# BMS12v3.net
KiCad netlist of a schematic drawn in EAGLE
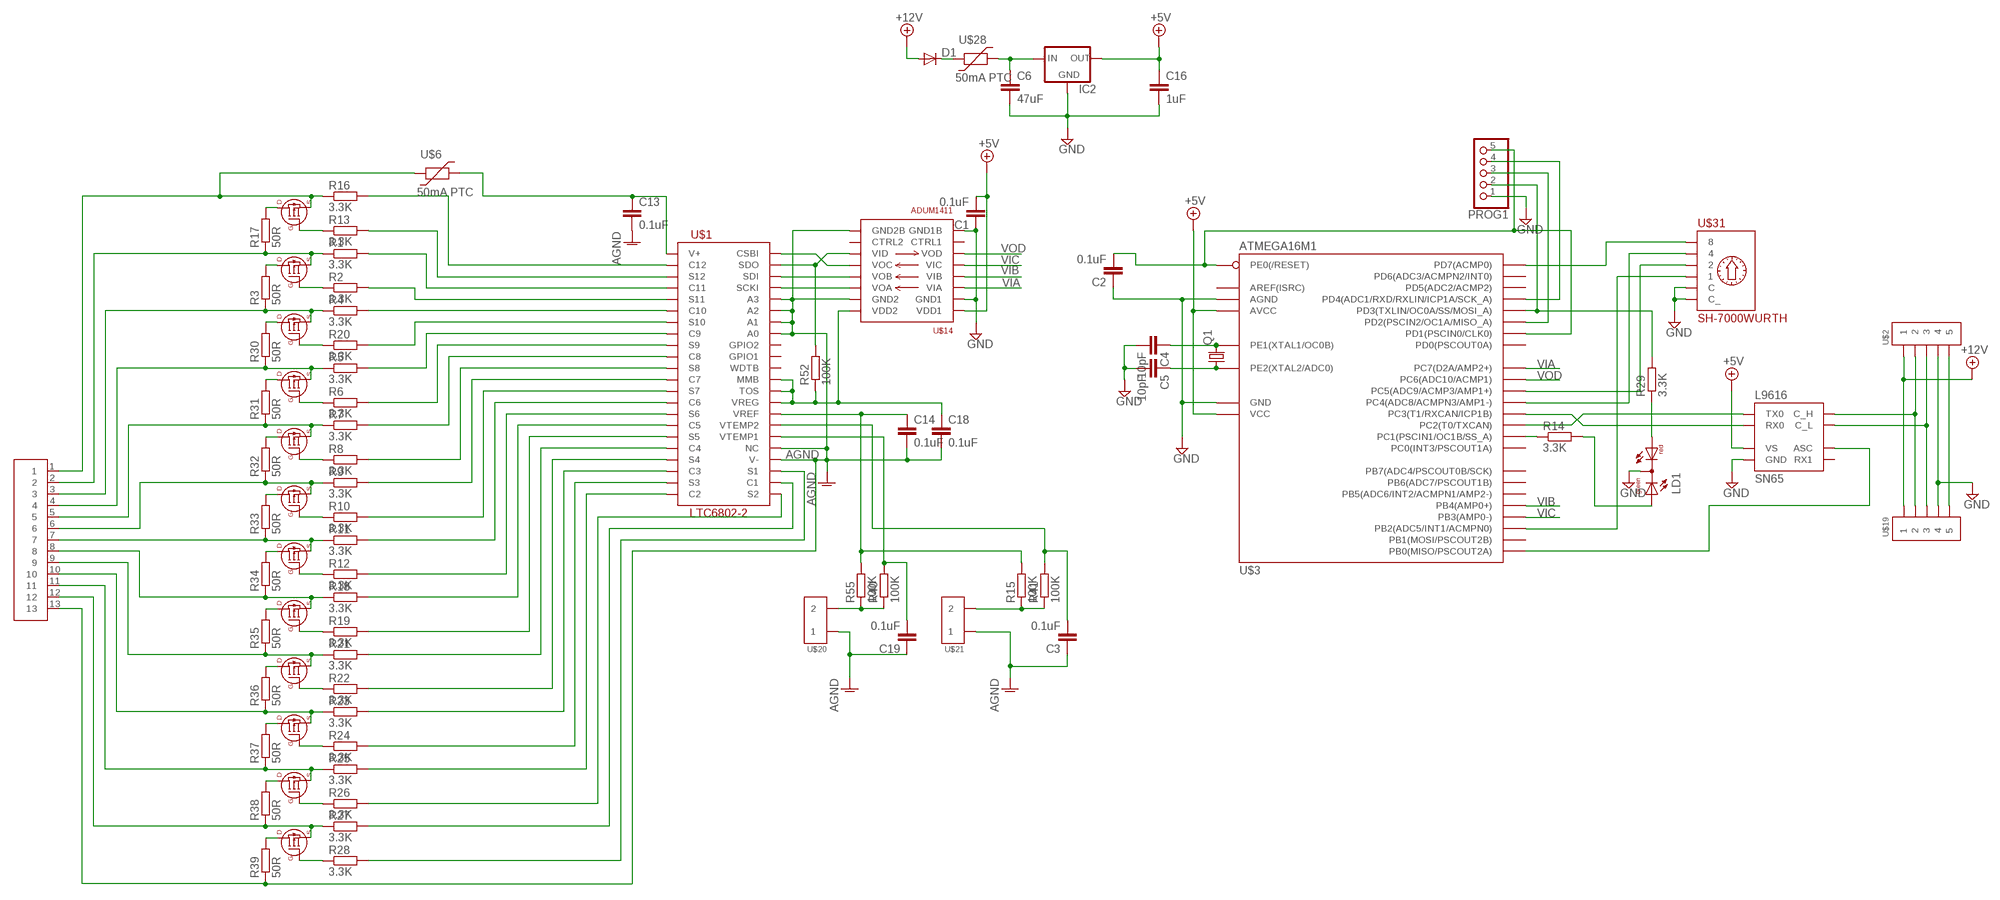
[diagram p0: schematic, sheet 1]

(export (version "E")
  (design (tool "Eeschema 10.0.6"))
  (components
    (comp (ref "C1")
      (value "0.1uF")
      (footprint "eagle-import:C0805")
      (libsource (lib "eagle-import") (part "C-EUC0805"))
    )
    (comp (ref "C2")
      (value "0.1uF")
      (footprint "eagle-import:C0805")
      (libsource (lib "eagle-import") (part "C-EUC0805"))
    )
    (comp (ref "C3")
      (value "0.1uF")
      (footprint "eagle-import:C0805")
      (libsource (lib "eagle-import") (part "C-EUC0805"))
    )
    (comp (ref "C4")
      (value "10pF")
      (footprint "eagle-import:C0805")
      (libsource (lib "eagle-import") (part "C-EUC0805"))
    )
    (comp (ref "C5")
      (value "10pF")
      (footprint "eagle-import:C0805")
      (libsource (lib "eagle-import") (part "C-EUC0805"))
    )
    (comp (ref "C6")
      (value "47uF")
      (footprint "eagle-import:C1206")
      (libsource (lib "eagle-import") (part "C-EUC1206"))
    )
    (comp (ref "C13")
      (value "0.1uF")
      (footprint "eagle-import:C0805")
      (libsource (lib "eagle-import") (part "C-EUC0805"))
    )
    (comp (ref "C14")
      (value "0.1uF")
      (footprint "eagle-import:C0805")
      (libsource (lib "eagle-import") (part "C-EUC0805"))
    )
    (comp (ref "C16")
      (value "1uF")
      (footprint "eagle-import:C0805")
      (libsource (lib "eagle-import") (part "C-EUC0805"))
    )
    (comp (ref "C18")
      (value "0.1uF")
      (footprint "eagle-import:C0805")
      (libsource (lib "eagle-import") (part "C-EUC0805"))
    )
    (comp (ref "C19")
      (value "0.1uF")
      (footprint "eagle-import:C0805")
      (libsource (lib "eagle-import") (part "C-EUC0805"))
    )
    (comp (ref "D1")
      (value "DIODE-SOD123")
      (footprint "eagle-import:SOD123")
      (libsource (lib "eagle-import") (part "DIODE-SOD123"))
    )
    (comp (ref "IC2")
      (value "78LXXSOT89")
      (footprint "eagle-import:SOT89R")
      (libsource (lib "eagle-import") (part "78LXXSOT89"))
    )
    (comp (ref "LD1")
      (value "DUOLED-RG-C")
      (footprint "eagle-import:DUOLED-C-5MM")
      (libsource (lib "eagle-import") (part "DUOLED-RG-C"))
    )
    (comp (ref "PROG1")
      (value "PINHD-1X5")
      (footprint "eagle-import:1X05")
      (libsource (lib "eagle-import") (part "PINHD-1X5"))
    )
    (comp (ref "Q1")
      (value "CRYSTALCTS406")
      (footprint "eagle-import:CTS406")
      (libsource (lib "eagle-import") (part "CRYSTALCTS406"))
    )
    (comp (ref "R1")
      (value "3.3K")
      (footprint "eagle-import:R0805")
      (libsource (lib "eagle-import") (part "R-EU_R0805"))
    )
    (comp (ref "R2")
      (value "3.3K")
      (footprint "eagle-import:R0805")
      (libsource (lib "eagle-import") (part "R-EU_R0805"))
    )
    (comp (ref "R3")
      (value "50R")
      (footprint "eagle-import:R2512")
      (libsource (lib "eagle-import") (part "R-EU_R2512"))
    )
    (comp (ref "R4")
      (value "3.3K")
      (footprint "eagle-import:R0805")
      (libsource (lib "eagle-import") (part "R-EU_R0805"))
    )
    (comp (ref "R5")
      (value "3.3K")
      (footprint "eagle-import:R0805")
      (libsource (lib "eagle-import") (part "R-EU_R0805"))
    )
    (comp (ref "R6")
      (value "3.3K")
      (footprint "eagle-import:R0805")
      (libsource (lib "eagle-import") (part "R-EU_R0805"))
    )
    (comp (ref "R7")
      (value "3.3K")
      (footprint "eagle-import:R0805")
      (libsource (lib "eagle-import") (part "R-EU_R0805"))
    )
    (comp (ref "R8")
      (value "3.3K")
      (footprint "eagle-import:R0805")
      (libsource (lib "eagle-import") (part "R-EU_R0805"))
    )
    (comp (ref "R9")
      (value "3.3K")
      (footprint "eagle-import:R0805")
      (libsource (lib "eagle-import") (part "R-EU_R0805"))
    )
    (comp (ref "R10")
      (value "3.3K")
      (footprint "eagle-import:R0805")
      (libsource (lib "eagle-import") (part "R-EU_R0805"))
    )
    (comp (ref "R11")
      (value "3.3K")
      (footprint "eagle-import:R0805")
      (libsource (lib "eagle-import") (part "R-EU_R0805"))
    )
    (comp (ref "R12")
      (value "3.3K")
      (footprint "eagle-import:R0805")
      (libsource (lib "eagle-import") (part "R-EU_R0805"))
    )
    (comp (ref "R13")
      (value "3.3K")
      (footprint "eagle-import:R0805")
      (libsource (lib "eagle-import") (part "R-EU_R0805"))
    )
    (comp (ref "R14")
      (value "3.3K")
      (footprint "eagle-import:R0805")
      (libsource (lib "eagle-import") (part "R-EU_R0805"))
    )
    (comp (ref "R15")
      (value "100K")
      (footprint "eagle-import:R0805")
      (libsource (lib "eagle-import") (part "R-EU_R0805"))
    )
    (comp (ref "R16")
      (value "3.3K")
      (footprint "eagle-import:R0805")
      (libsource (lib "eagle-import") (part "R-EU_R0805"))
    )
    (comp (ref "R17")
      (value "50R")
      (footprint "eagle-import:R2512")
      (libsource (lib "eagle-import") (part "R-EU_R2512"))
    )
    (comp (ref "R18")
      (value "3.3K")
      (footprint "eagle-import:R0805")
      (libsource (lib "eagle-import") (part "R-EU_R0805"))
    )
    (comp (ref "R19")
      (value "3.3K")
      (footprint "eagle-import:R0805")
      (libsource (lib "eagle-import") (part "R-EU_R0805"))
    )
    (comp (ref "R20")
      (value "3.3K")
      (footprint "eagle-import:R0805")
      (libsource (lib "eagle-import") (part "R-EU_R0805"))
    )
    (comp (ref "R21")
      (value "3.3K")
      (footprint "eagle-import:R0805")
      (libsource (lib "eagle-import") (part "R-EU_R0805"))
    )
    (comp (ref "R22")
      (value "3.3K")
      (footprint "eagle-import:R0805")
      (libsource (lib "eagle-import") (part "R-EU_R0805"))
    )
    (comp (ref "R23")
      (value "3.3K")
      (footprint "eagle-import:R0805")
      (libsource (lib "eagle-import") (part "R-EU_R0805"))
    )
    (comp (ref "R24")
      (value "3.3K")
      (footprint "eagle-import:R0805")
      (libsource (lib "eagle-import") (part "R-EU_R0805"))
    )
    (comp (ref "R25")
      (value "3.3K")
      (footprint "eagle-import:R0805")
      (libsource (lib "eagle-import") (part "R-EU_R0805"))
    )
    (comp (ref "R26")
      (value "3.3K")
      (footprint "eagle-import:R0805")
      (libsource (lib "eagle-import") (part "R-EU_R0805"))
    )
    (comp (ref "R27")
      (value "3.3K")
      (footprint "eagle-import:R0805")
      (libsource (lib "eagle-import") (part "R-EU_R0805"))
    )
    (comp (ref "R28")
      (value "3.3K")
      (footprint "eagle-import:R0805")
      (libsource (lib "eagle-import") (part "R-EU_R0805"))
    )
    (comp (ref "R29")
      (value "3.3K")
      (footprint "eagle-import:R0805")
      (libsource (lib "eagle-import") (part "R-EU_R0805"))
    )
    (comp (ref "R30")
      (value "50R")
      (footprint "eagle-import:R2512")
      (libsource (lib "eagle-import") (part "R-EU_R2512"))
    )
    (comp (ref "R31")
      (value "50R")
      (footprint "eagle-import:R2512")
      (libsource (lib "eagle-import") (part "R-EU_R2512"))
    )
    (comp (ref "R32")
      (value "50R")
      (footprint "eagle-import:R2512")
      (libsource (lib "eagle-import") (part "R-EU_R2512"))
    )
    (comp (ref "R33")
      (value "50R")
      (footprint "eagle-import:R2512")
      (libsource (lib "eagle-import") (part "R-EU_R2512"))
    )
    (comp (ref "R34")
      (value "50R")
      (footprint "eagle-import:R2512")
      (libsource (lib "eagle-import") (part "R-EU_R2512"))
    )
    (comp (ref "R35")
      (value "50R")
      (footprint "eagle-import:R2512")
      (libsource (lib "eagle-import") (part "R-EU_R2512"))
    )
    (comp (ref "R36")
      (value "50R")
      (footprint "eagle-import:R2512")
      (libsource (lib "eagle-import") (part "R-EU_R2512"))
    )
    (comp (ref "R37")
      (value "50R")
      (footprint "eagle-import:R2512")
      (libsource (lib "eagle-import") (part "R-EU_R2512"))
    )
    (comp (ref "R38")
      (value "50R")
      (footprint "eagle-import:R2512")
      (libsource (lib "eagle-import") (part "R-EU_R2512"))
    )
    (comp (ref "R39")
      (value "50R")
      (footprint "eagle-import:R2512")
      (libsource (lib "eagle-import") (part "R-EU_R2512"))
    )
    (comp (ref "R40")
      (value "100K")
      (footprint "eagle-import:R0805")
      (libsource (lib "eagle-import") (part "R-EU_R0805"))
    )
    (comp (ref "R41")
      (value "100K")
      (footprint "eagle-import:R0805")
      (libsource (lib "eagle-import") (part "R-EU_R0805"))
    )
    (comp (ref "R52")
      (value "100K")
      (footprint "eagle-import:R0805")
      (libsource (lib "eagle-import") (part "R-EU_R0805"))
    )
    (comp (ref "R55")
      (value "100K")
      (footprint "eagle-import:R0805")
      (libsource (lib "eagle-import") (part "R-EU_R0805"))
    )
    (comp (ref "SN65")
      (value "L9616")
      (footprint "eagle-import:SOIC8")
      (libsource (lib "eagle-import") (part "L9616"))
    )
    (comp (ref "U$1")
      (value "LTC6802-2")
      (footprint "eagle-import:SSOP-44")
      (libsource (lib "eagle-import") (part "LTC6802-2"))
    )
    (comp (ref "U$2")
      (value "MOLEX-39502-1005")
      (footprint "eagle-import:MOLEX-39502-1005")
      (libsource (lib "eagle-import") (part "MOLEX-39502-1005"))
    )
    (comp (ref "U$3")
      (value "ATMEGA16M1")
      (footprint "eagle-import:TQFP32")
      (libsource (lib "eagle-import") (part "ATMEGA16M1"))
    )
    (comp (ref "U$4")
      (value "SI2351DS")
      (footprint "eagle-import:SOT23")
      (libsource (lib "eagle-import") (part "SI2351DS"))
    )
    (comp (ref "U$5")
      (value "SI2351DS")
      (footprint "eagle-import:SOT23")
      (libsource (lib "eagle-import") (part "SI2351DS"))
    )
    (comp (ref "U$6")
      (value "50mA PTC")
      (footprint "eagle-import:1206")
      (libsource (lib "eagle-import") (part "1206_POLYSWITCH"))
    )
    (comp (ref "U$7")
      (value "SI2351DS")
      (footprint "eagle-import:SOT23")
      (libsource (lib "eagle-import") (part "SI2351DS"))
    )
    (comp (ref "U$8")
      (value "SI2351DS")
      (footprint "eagle-import:SOT23")
      (libsource (lib "eagle-import") (part "SI2351DS"))
    )
    (comp (ref "U$9")
      (value "SI2351DS")
      (footprint "eagle-import:SOT23")
      (libsource (lib "eagle-import") (part "SI2351DS"))
    )
    (comp (ref "U$10")
      (value "SI2351DS")
      (footprint "eagle-import:SOT23")
      (libsource (lib "eagle-import") (part "SI2351DS"))
    )
    (comp (ref "U$11")
      (value "SI2351DS")
      (footprint "eagle-import:SOT23")
      (libsource (lib "eagle-import") (part "SI2351DS"))
    )
    (comp (ref "U$12")
      (value "SI2351DS")
      (footprint "eagle-import:SOT23")
      (libsource (lib "eagle-import") (part "SI2351DS"))
    )
    (comp (ref "U$13")
      (value "SI2351DS")
      (footprint "eagle-import:SOT23")
      (libsource (lib "eagle-import") (part "SI2351DS"))
    )
    (comp (ref "U$14")
      (value "ADUM1411")
      (footprint "eagle-import:SOIC16W")
      (libsource (lib "eagle-import") (part "ADUM1411"))
    )
    (comp (ref "U$15")
      (value "SI2351DS")
      (footprint "eagle-import:SOT23")
      (libsource (lib "eagle-import") (part "SI2351DS"))
    )
    (comp (ref "U$16")
      (value "SI2351DS")
      (footprint "eagle-import:SOT23")
      (libsource (lib "eagle-import") (part "SI2351DS"))
    )
    (comp (ref "U$17")
      (value "SI2351DS")
      (footprint "eagle-import:SOT23")
      (libsource (lib "eagle-import") (part "SI2351DS"))
    )
    (comp (ref "U$18")
      (value "MOLEX_TERM_BLOCK_13")
      (footprint "eagle-import:MOLEX_TERM_BLOCK_13")
      (libsource (lib "eagle-import") (part "MOLEX_TERM_BLOCK_13"))
    )
    (comp (ref "U$19")
      (value "MOLEX-39502-1005")
      (footprint "eagle-import:MOLEX-39502-1005")
      (libsource (lib "eagle-import") (part "MOLEX-39502-1005"))
    )
    (comp (ref "U$20")
      (value "MOLEX-39502-1002")
      (footprint "eagle-import:MOLEX-39502-1002")
      (libsource (lib "eagle-import") (part "MOLEX-39502-1002"))
    )
    (comp (ref "U$21")
      (value "MOLEX-39502-1002")
      (footprint "eagle-import:MOLEX-39502-1002")
      (libsource (lib "eagle-import") (part "MOLEX-39502-1002"))
    )
    (comp (ref "U$28")
      (value "50mA PTC")
      (footprint "eagle-import:1206")
      (libsource (lib "eagle-import") (part "1206_POLYSWITCH"))
    )
    (comp (ref "U$31")
      (value "SH-7000WURTH")
      (footprint "eagle-import:WS-ROTV")
      (libsource (lib "eagle-import") (part "SH-7000WURTH"))
    )
  )
  (nets
    (net (code "1") (name "+5V") (class "Default")
      (node (ref "C1") (pin "2") (pinfunction "2_2") (pintype "passive"))
      (node (ref "C16") (pin "1") (pinfunction "1_1") (pintype "passive"))
      (node (ref "IC2") (pin "2") (pinfunction "OUT_2") (pintype "passive"))
      (node (ref "SN65") (pin "P$3") (pinfunction "VS_P$3") (pintype "bidirectional"))
      (node (ref "U$14") (pin "1") (pinfunction "VDD1_1") (pintype "bidirectional"))
      (node (ref "U$3") (pin "19") (pinfunction "AVCC_19") (pintype "bidirectional"))
      (node (ref "U$3") (pin "4") (pinfunction "VCC_4") (pintype "bidirectional"))
    )
    (net (code "2") (name "+12V") (class "Default")
      (node (ref "D1") (pin "A") (pinfunction "A_A") (pintype "passive"))
      (node (ref "U$19") (pin "1") (pinfunction "1_1") (pintype "bidirectional"))
      (node (ref "U$2") (pin "1") (pinfunction "1_1") (pintype "bidirectional"))
    )
    (net (code "3") (name "/VIA") (class "Default")
      (node (ref "U$14") (pin "3") (pinfunction "VIA_3") (pintype "bidirectional"))
      (node (ref "U$3") (pin "25") (pinfunction "PC7(D2A/AMP2+)_25") (pintype "bidirectional"))
    )
    (net (code "4") (name "/VIB") (class "Default")
      (node (ref "U$14") (pin "4") (pinfunction "VIB_4") (pintype "bidirectional"))
      (node (ref "U$3") (pin "24") (pinfunction "PB4(AMP0+)_24") (pintype "bidirectional"))
    )
    (net (code "5") (name "/VIC") (class "Default")
      (node (ref "U$14") (pin "5") (pinfunction "VIC_5") (pintype "bidirectional"))
      (node (ref "U$3") (pin "23") (pinfunction "PB3(AMP0-)_23") (pintype "bidirectional"))
    )
    (net (code "6") (name "/VOD") (class "Default")
      (node (ref "U$14") (pin "6") (pinfunction "VOD_6") (pintype "bidirectional"))
      (node (ref "U$3") (pin "22") (pinfunction "PC6(ADC10/ACMP1)_22") (pintype "bidirectional"))
    )
    (net (code "7") (name "AGND") (class "Default")
      (node (ref "C13") (pin "2") (pinfunction "2_2") (pintype "passive"))
      (node (ref "C14") (pin "2") (pinfunction "2_2") (pintype "passive"))
      (node (ref "C18") (pin "2") (pinfunction "2_2") (pintype "passive"))
      (node (ref "C19") (pin "1") (pinfunction "1_1") (pintype "passive"))
      (node (ref "C3") (pin "1") (pinfunction "1_1") (pintype "passive"))
      (node (ref "R39") (pin "1") (pinfunction "1_1") (pintype "passive"))
      (node (ref "U$1") (pin "26") (pinfunction "V-_26") (pintype "bidirectional"))
      (node (ref "U$1") (pin "27") (pinfunction "NC_27") (pintype "bidirectional"))
      (node (ref "U$1") (pin "37") (pinfunction "A0_37") (pintype "bidirectional"))
      (node (ref "U$1") (pin "38") (pinfunction "A1_38") (pintype "bidirectional"))
      (node (ref "U$1") (pin "39") (pinfunction "A2_39") (pintype "bidirectional"))
      (node (ref "U$1") (pin "40") (pinfunction "A3_40") (pintype "bidirectional"))
      (node (ref "U$14") (pin "15") (pinfunction "GND2_15") (pintype "bidirectional"))
      (node (ref "U$14") (pin "9") (pinfunction "GND2B_9") (pintype "bidirectional"))
      (node (ref "U$18") (pin "13") (pinfunction "13_13") (pintype "bidirectional"))
      (node (ref "U$20") (pin "1") (pinfunction "1_1") (pintype "bidirectional"))
      (node (ref "U$21") (pin "1") (pinfunction "1_1") (pintype "bidirectional"))
    )
    (net (code "8") (name "GND") (class "Default")
      (node (ref "C1") (pin "1") (pinfunction "1_1") (pintype "passive"))
      (node (ref "C16") (pin "2") (pinfunction "2_2") (pintype "passive"))
      (node (ref "C2") (pin "1") (pinfunction "1_1") (pintype "passive"))
      (node (ref "C4") (pin "2") (pinfunction "2_2") (pintype "passive"))
      (node (ref "C5") (pin "2") (pinfunction "2_2") (pintype "passive"))
      (node (ref "C6") (pin "2") (pinfunction "2_2") (pintype "passive"))
      (node (ref "IC2") (pin "4") (pinfunction "GND_4") (pintype "input"))
      (node (ref "LD1") (pin "C") (pinfunction "C_C") (pintype "passive"))
      (node (ref "PROG1") (pin "1") (pinfunction "1_1") (pintype "passive"))
      (node (ref "SN65") (pin "P$2") (pinfunction "GND_P$2") (pintype "bidirectional"))
      (node (ref "U$14") (pin "2") (pinfunction "GND1_2") (pintype "bidirectional"))
      (node (ref "U$14") (pin "8") (pinfunction "GND1B_8") (pintype "bidirectional"))
      (node (ref "U$19") (pin "4") (pinfunction "4_4") (pintype "bidirectional"))
      (node (ref "U$2") (pin "4") (pinfunction "4_4") (pintype "bidirectional"))
      (node (ref "U$3") (pin "20") (pinfunction "AGND_20") (pintype "bidirectional"))
      (node (ref "U$3") (pin "5") (pinfunction "GND_5") (pintype "bidirectional"))
      (node (ref "U$31") (pin "C") (pinfunction "C_C") (pintype "bidirectional"))
      (node (ref "U$31") (pin "C2") (pinfunction "C__C2") (pintype "bidirectional"))
    )
    (net (code "9") (name "Net-(D1-PadC)") (class "Default")
      (node (ref "D1") (pin "C") (pinfunction "C_C") (pintype "passive"))
      (node (ref "U$28") (pin "P$1") (pinfunction "P$1_P$1") (pintype "bidirectional"))
    )
    (net (code "10") (name "Net-(IC2-IN)") (class "Default")
      (node (ref "C6") (pin "1") (pinfunction "1_1") (pintype "passive"))
      (node (ref "IC2") (pin "1") (pinfunction "IN_1") (pintype "input"))
      (node (ref "U$28") (pin "P$2") (pinfunction "P$2_P$2") (pintype "bidirectional"))
    )
    (net (code "11") (name "Net-(LD1-AG)") (class "Default")
      (node (ref "LD1") (pin "AX") (pinfunction "AG_AX") (pintype "passive"))
      (node (ref "R14") (pin "2") (pinfunction "2_2") (pintype "passive"))
    )
    (net (code "12") (name "Net-(LD1-PadAR)") (class "Default")
      (node (ref "LD1") (pin "AR") (pinfunction "AR_AR") (pintype "passive"))
      (node (ref "R29") (pin "1") (pinfunction "1_1") (pintype "passive"))
    )
    (net (code "13") (name "Net-(Q1-2)") (class "Default")
      (node (ref "C4") (pin "1") (pinfunction "1_1") (pintype "passive"))
      (node (ref "Q1") (pin "3") (pinfunction "2_3") (pintype "passive"))
      (node (ref "U$3") (pin "10") (pinfunction "PE1(XTAL1/OC0B)_10") (pintype "bidirectional"))
    )
    (net (code "14") (name "Net-(R15-Pad1)") (class "Default")
      (node (ref "R15") (pin "1") (pinfunction "1_1") (pintype "passive"))
      (node (ref "R41") (pin "1") (pinfunction "1_1") (pintype "passive"))
      (node (ref "U$21") (pin "2") (pinfunction "2_2") (pintype "bidirectional"))
    )
    (net (code "15") (name "Net-(R40-Pad1)") (class "Default")
      (node (ref "R40") (pin "1") (pinfunction "1_1") (pintype "passive"))
      (node (ref "R55") (pin "1") (pinfunction "1_1") (pintype "passive"))
      (node (ref "U$20") (pin "2") (pinfunction "2_2") (pintype "bidirectional"))
    )
    (net (code "16") (name "Net-(SN65-ASC)") (class "Default")
      (node (ref "SN65") (pin "P$8") (pinfunction "ASC_P$8") (pintype "bidirectional"))
      (node (ref "U$3") (pin "8") (pinfunction "PB0(MISO/PSCOUT2A)_8") (pintype "bidirectional"))
    )
    (net (code "17") (name "Net-(SN65-C_H)") (class "Default")
      (node (ref "SN65") (pin "P$7") (pinfunction "C_H_P$7") (pintype "bidirectional"))
      (node (ref "U$19") (pin "2") (pinfunction "2_2") (pintype "bidirectional"))
      (node (ref "U$2") (pin "2") (pinfunction "2_2") (pintype "bidirectional"))
    )
    (net (code "18") (name "Net-(SN65-C_L)") (class "Default")
      (node (ref "SN65") (pin "P$6") (pinfunction "C_L_P$6") (pintype "bidirectional"))
      (node (ref "U$19") (pin "3") (pinfunction "3_3") (pintype "bidirectional"))
      (node (ref "U$2") (pin "3") (pinfunction "3_3") (pintype "bidirectional"))
    )
    (net (code "19") (name "Net-(SN65-RX0)") (class "Default")
      (node (ref "SN65") (pin "P$4") (pinfunction "RX0_P$4") (pintype "bidirectional"))
      (node (ref "U$3") (pin "7") (pinfunction "PC3(T1/RXCAN/ICP1B)_7") (pintype "bidirectional"))
    )
    (net (code "20") (name "Net-(SN65-TX0)") (class "Default")
      (node (ref "SN65") (pin "P$1") (pinfunction "TX0_P$1") (pintype "bidirectional"))
      (node (ref "U$3") (pin "6") (pinfunction "PC2(T0/TXCAN)_6") (pintype "bidirectional"))
    )
    (net (code "21") (name "Net-(U$1-C1)") (class "Default")
      (node (ref "R27") (pin "2") (pinfunction "2_2") (pintype "passive"))
      (node (ref "U$1") (pin "24") (pinfunction "C1_24") (pintype "bidirectional"))
    )
    (net (code "22") (name "Net-(U$1-C2)") (class "Default")
      (node (ref "R25") (pin "2") (pinfunction "2_2") (pintype "passive"))
      (node (ref "U$1") (pin "22") (pinfunction "C2_22") (pintype "bidirectional"))
    )
    (net (code "23") (name "Net-(U$1-C3)") (class "Default")
      (node (ref "R23") (pin "2") (pinfunction "2_2") (pintype "passive"))
      (node (ref "U$1") (pin "20") (pinfunction "C3_20") (pintype "bidirectional"))
    )
    (net (code "24") (name "Net-(U$1-C4)") (class "Default")
      (node (ref "R21") (pin "2") (pinfunction "2_2") (pintype "passive"))
      (node (ref "U$1") (pin "18") (pinfunction "C4_18") (pintype "bidirectional"))
    )
    (net (code "25") (name "Net-(U$1-C5)") (class "Default")
      (node (ref "R18") (pin "2") (pinfunction "2_2") (pintype "passive"))
      (node (ref "U$1") (pin "16") (pinfunction "C5_16") (pintype "bidirectional"))
    )
    (net (code "26") (name "Net-(U$1-C6)") (class "Default")
      (node (ref "R11") (pin "2") (pinfunction "2_2") (pintype "passive"))
      (node (ref "U$1") (pin "14") (pinfunction "C6_14") (pintype "bidirectional"))
    )
    (net (code "27") (name "Net-(U$1-C7)") (class "Default")
      (node (ref "R9") (pin "2") (pinfunction "2_2") (pintype "passive"))
      (node (ref "U$1") (pin "12") (pinfunction "C7_12") (pintype "bidirectional"))
    )
    (net (code "28") (name "Net-(U$1-C8)") (class "Default")
      (node (ref "R7") (pin "2") (pinfunction "2_2") (pintype "passive"))
      (node (ref "U$1") (pin "10") (pinfunction "C8_10") (pintype "bidirectional"))
    )
    (net (code "29") (name "Net-(U$1-C9)") (class "Default")
      (node (ref "R5") (pin "2") (pinfunction "2_2") (pintype "passive"))
      (node (ref "U$1") (pin "8") (pinfunction "C9_8") (pintype "bidirectional"))
    )
    (net (code "30") (name "Net-(U$1-C10)") (class "Default")
      (node (ref "R4") (pin "2") (pinfunction "2_2") (pintype "passive"))
      (node (ref "U$1") (pin "6") (pinfunction "C10_6") (pintype "bidirectional"))
    )
    (net (code "31") (name "Net-(U$1-C11)") (class "Default")
      (node (ref "R1") (pin "2") (pinfunction "2_2") (pintype "passive"))
      (node (ref "U$1") (pin "4") (pinfunction "C11_4") (pintype "bidirectional"))
    )
    (net (code "32") (name "Net-(U$1-C12)") (class "Default")
      (node (ref "R16") (pin "2") (pinfunction "2_2") (pintype "passive"))
      (node (ref "U$1") (pin "2") (pinfunction "C12_2") (pintype "bidirectional"))
    )
    (net (code "33") (name "Net-(U$1-CSBI)") (class "Default")
      (node (ref "U$1") (pin "44") (pinfunction "CSBI_44") (pintype "bidirectional"))
      (node (ref "U$14") (pin "12") (pinfunction "VOC_12") (pintype "bidirectional"))
    )
    (net (code "34") (name "Net-(U$1-MMB)") (class "Default")
      (node (ref "C18") (pin "1") (pinfunction "1_1") (pintype "passive"))
      (node (ref "R52") (pin "1") (pinfunction "1_1") (pintype "passive"))
      (node (ref "U$1") (pin "31") (pinfunction "VREG_31") (pintype "bidirectional"))
      (node (ref "U$1") (pin "32") (pinfunction "TOS_32") (pintype "bidirectional"))
      (node (ref "U$1") (pin "33") (pinfunction "MMB_33") (pintype "bidirectional"))
      (node (ref "U$14") (pin "16") (pinfunction "VDD2_16") (pintype "bidirectional"))
    )
    (net (code "35") (name "Net-(U$1-S1)") (class "Default")
      (node (ref "R28") (pin "2") (pinfunction "2_2") (pintype "passive"))
      (node (ref "U$1") (pin "25") (pinfunction "S1_25") (pintype "bidirectional"))
    )
    (net (code "36") (name "Net-(U$1-S2)") (class "Default")
      (node (ref "R26") (pin "2") (pinfunction "2_2") (pintype "passive"))
      (node (ref "U$1") (pin "23") (pinfunction "S2_23") (pintype "bidirectional"))
    )
    (net (code "37") (name "Net-(U$1-S3)") (class "Default")
      (node (ref "R24") (pin "2") (pinfunction "2_2") (pintype "passive"))
      (node (ref "U$1") (pin "21") (pinfunction "S3_21") (pintype "bidirectional"))
    )
    (net (code "38") (name "Net-(U$1-S4)") (class "Default")
      (node (ref "R22") (pin "2") (pinfunction "2_2") (pintype "passive"))
      (node (ref "U$1") (pin "19") (pinfunction "S4_19") (pintype "bidirectional"))
    )
    (net (code "39") (name "Net-(U$1-S5)") (class "Default")
      (node (ref "R19") (pin "2") (pinfunction "2_2") (pintype "passive"))
      (node (ref "U$1") (pin "17") (pinfunction "S5_17") (pintype "bidirectional"))
    )
    (net (code "40") (name "Net-(U$1-S6)") (class "Default")
      (node (ref "R12") (pin "2") (pinfunction "2_2") (pintype "passive"))
      (node (ref "U$1") (pin "15") (pinfunction "S6_15") (pintype "bidirectional"))
    )
    (net (code "41") (name "Net-(U$1-S7)") (class "Default")
      (node (ref "R10") (pin "2") (pinfunction "2_2") (pintype "passive"))
      (node (ref "U$1") (pin "13") (pinfunction "S7_13") (pintype "bidirectional"))
    )
    (net (code "42") (name "Net-(U$1-S8)") (class "Default")
      (node (ref "R8") (pin "2") (pinfunction "2_2") (pintype "passive"))
      (node (ref "U$1") (pin "11") (pinfunction "S8_11") (pintype "bidirectional"))
    )
    (net (code "43") (name "Net-(U$1-S9)") (class "Default")
      (node (ref "R6") (pin "2") (pinfunction "2_2") (pintype "passive"))
      (node (ref "U$1") (pin "9") (pinfunction "S9_9") (pintype "bidirectional"))
    )
    (net (code "44") (name "Net-(U$1-S10)") (class "Default")
      (node (ref "R20") (pin "2") (pinfunction "2_2") (pintype "passive"))
      (node (ref "U$1") (pin "7") (pinfunction "S10_7") (pintype "bidirectional"))
    )
    (net (code "45") (name "Net-(U$1-S11)") (class "Default")
      (node (ref "R2") (pin "2") (pinfunction "2_2") (pintype "passive"))
      (node (ref "U$1") (pin "5") (pinfunction "S11_5") (pintype "bidirectional"))
    )
    (net (code "46") (name "Net-(U$1-S12)") (class "Default")
      (node (ref "R13") (pin "2") (pinfunction "2_2") (pintype "passive"))
      (node (ref "U$1") (pin "3") (pinfunction "S12_3") (pintype "bidirectional"))
    )
    (net (code "47") (name "Net-(U$1-SCKI)") (class "Default")
      (node (ref "U$1") (pin "41") (pinfunction "SCKI_41") (pintype "bidirectional"))
      (node (ref "U$14") (pin "14") (pinfunction "VOA_14") (pintype "bidirectional"))
    )
    (net (code "48") (name "Net-(U$1-SDI)") (class "Default")
      (node (ref "U$1") (pin "42") (pinfunction "SDI_42") (pintype "bidirectional"))
      (node (ref "U$14") (pin "13") (pinfunction "VOB_13") (pintype "bidirectional"))
    )
    (net (code "49") (name "Net-(U$1-SDO)") (class "Default")
      (node (ref "R52") (pin "2") (pinfunction "2_2") (pintype "passive"))
      (node (ref "U$1") (pin "43") (pinfunction "SDO_43") (pintype "bidirectional"))
      (node (ref "U$14") (pin "11") (pinfunction "VID_11") (pintype "bidirectional"))
    )
    (net (code "50") (name "Net-(U$1-V+)") (class "Default")
      (node (ref "C13") (pin "1") (pinfunction "1_1") (pintype "passive"))
      (node (ref "U$1") (pin "1") (pinfunction "V+_1") (pintype "bidirectional"))
      (node (ref "U$6") (pin "P$2") (pinfunction "P$2_P$2") (pintype "bidirectional"))
    )
    (net (code "51") (name "Net-(U$1-VREF)") (class "Default")
      (node (ref "C14") (pin "1") (pinfunction "1_1") (pintype "passive"))
      (node (ref "R15") (pin "2") (pinfunction "2_2") (pintype "passive"))
      (node (ref "R55") (pin "2") (pinfunction "2_2") (pintype "passive"))
      (node (ref "U$1") (pin "30") (pinfunction "VREF_30") (pintype "bidirectional"))
    )
    (net (code "52") (name "Net-(U$1-VTEMP1)") (class "Default")
      (node (ref "C19") (pin "2") (pinfunction "2_2") (pintype "passive"))
      (node (ref "R40") (pin "2") (pinfunction "2_2") (pintype "passive"))
      (node (ref "U$1") (pin "28") (pinfunction "VTEMP1_28") (pintype "bidirectional"))
    )
    (net (code "53") (name "Net-(U$1-VTEMP2)") (class "Default")
      (node (ref "C3") (pin "2") (pinfunction "2_2") (pintype "passive"))
      (node (ref "R41") (pin "2") (pinfunction "2_2") (pintype "passive"))
      (node (ref "U$1") (pin "29") (pinfunction "VTEMP2_29") (pintype "bidirectional"))
    )
    (net (code "54") (name "Net-(U$3-PB2(ADC5{slash}INT1{slash}ACMPN0))") (class "Default")
      (node (ref "U$3") (pin "16") (pinfunction "PB2(ADC5/INT1/ACMPN0)_16") (pintype "bidirectional"))
      (node (ref "U$31") (pin "1") (pinfunction "1_1") (pintype "bidirectional"))
    )
    (net (code "55") (name "Net-(U$3-PC1(PSCIN1{slash}OC1B{slash}SS_A))") (class "Default")
      (node (ref "R14") (pin "1") (pinfunction "1_1") (pintype "passive"))
      (node (ref "U$3") (pin "3") (pinfunction "PC1(PSCIN1/OC1B/SS_A)_3") (pintype "bidirectional"))
    )
    (net (code "56") (name "Net-(U$3-PC4(ADC8{slash}ACMPN3{slash}AMP1-))") (class "Default")
      (node (ref "U$3") (pin "17") (pinfunction "PC4(ADC8/ACMPN3/AMP1-)_17") (pintype "bidirectional"))
      (node (ref "U$31") (pin "4") (pinfunction "4_4") (pintype "bidirectional"))
    )
    (net (code "57") (name "Net-(U$3-PC5(ADC9{slash}ACMP3{slash}AMP1+))") (class "Default")
      (node (ref "U$3") (pin "18") (pinfunction "PC5(ADC9/ACMP3/AMP1+)_18") (pintype "bidirectional"))
      (node (ref "U$31") (pin "2") (pinfunction "2_2") (pintype "bidirectional"))
    )
    (net (code "58") (name "Net-(U$3-PD1(PSCIN0{slash}CLK0))") (class "Default")
      (node (ref "C2") (pin "2") (pinfunction "2_2") (pintype "passive"))
      (node (ref "PROG1") (pin "5") (pinfunction "5_5") (pintype "passive"))
      (node (ref "U$3") (pin "31") (pinfunction "PE0(/RESET)_31") (pintype "bidirectional"))
      (node (ref "U$3") (pin "32") (pinfunction "PD1(PSCIN0/CLK0)_32") (pintype "bidirectional"))
    )
    (net (code "59") (name "Net-(U$3-PD2(PSCIN2{slash}OC1A{slash}MISO_A))") (class "Default")
      (node (ref "PROG1") (pin "3") (pinfunction "3_3") (pintype "passive"))
      (node (ref "U$3") (pin "1") (pinfunction "PD2(PSCIN2/OC1A/MISO_A)_1") (pintype "bidirectional"))
    )
    (net (code "60") (name "Net-(U$3-PD3(TXLIN{slash}OC0A{slash}SS{slash}MOSI_A))") (class "Default")
      (node (ref "PROG1") (pin "2") (pinfunction "2_2") (pintype "passive"))
      (node (ref "R29") (pin "2") (pinfunction "2_2") (pintype "passive"))
      (node (ref "U$3") (pin "2") (pinfunction "PD3(TXLIN/OC0A/SS/MOSI_A)_2") (pintype "bidirectional"))
    )
    (net (code "61") (name "Net-(U$3-PD4(ADC1{slash}RXD{slash}RXLIN{slash}ICP1A{slash}SCK_A))") (class "Default")
      (node (ref "PROG1") (pin "4") (pinfunction "4_4") (pintype "passive"))
      (node (ref "U$3") (pin "12") (pinfunction "PD4(ADC1/RXD/RXLIN/ICP1A/SCK_A)_12") (pintype "bidirectional"))
    )
    (net (code "62") (name "Net-(U$3-PD7(ACMP0))") (class "Default")
      (node (ref "U$3") (pin "15") (pinfunction "PD7(ACMP0)_15") (pintype "bidirectional"))
      (node (ref "U$31") (pin "8") (pinfunction "8_8") (pintype "bidirectional"))
    )
    (net (code "63") (name "Net-(U$3-PE2(XTAL2{slash}ADC0))") (class "Default")
      (node (ref "C5") (pin "1") (pinfunction "1_1") (pintype "passive"))
      (node (ref "Q1") (pin "1") (pinfunction "1_1") (pintype "passive"))
      (node (ref "U$3") (pin "11") (pinfunction "PE2(XTAL2/ADC0)_11") (pintype "bidirectional"))
    )
    (net (code "64") (name "Net-(U$4-D)") (class "Default")
      (node (ref "R17") (pin "2") (pinfunction "2_2") (pintype "passive"))
      (node (ref "U$4") (pin "P$3") (pinfunction "D_P$3") (pintype "bidirectional"))
    )
    (net (code "65") (name "Net-(U$4-G)") (class "Default")
      (node (ref "R13") (pin "1") (pinfunction "1_1") (pintype "passive"))
      (node (ref "U$4") (pin "P$1") (pinfunction "G_P$1") (pintype "bidirectional"))
    )
    (net (code "66") (name "Net-(U$4-S)") (class "Default")
      (node (ref "R16") (pin "1") (pinfunction "1_1") (pintype "passive"))
      (node (ref "U$18") (pin "1") (pinfunction "1_1") (pintype "bidirectional"))
      (node (ref "U$4") (pin "P$2") (pinfunction "S_P$2") (pintype "bidirectional"))
      (node (ref "U$6") (pin "P$1") (pinfunction "P$1_P$1") (pintype "bidirectional"))
    )
    (net (code "67") (name "Net-(U$5-D)") (class "Default")
      (node (ref "R3") (pin "2") (pinfunction "2_2") (pintype "passive"))
      (node (ref "U$5") (pin "P$3") (pinfunction "D_P$3") (pintype "bidirectional"))
    )
    (net (code "68") (name "Net-(U$5-G)") (class "Default")
      (node (ref "R2") (pin "1") (pinfunction "1_1") (pintype "passive"))
      (node (ref "U$5") (pin "P$1") (pinfunction "G_P$1") (pintype "bidirectional"))
    )
    (net (code "69") (name "Net-(U$5-S)") (class "Default")
      (node (ref "R1") (pin "1") (pinfunction "1_1") (pintype "passive"))
      (node (ref "R17") (pin "1") (pinfunction "1_1") (pintype "passive"))
      (node (ref "U$18") (pin "2") (pinfunction "2_2") (pintype "bidirectional"))
      (node (ref "U$5") (pin "P$2") (pinfunction "S_P$2") (pintype "bidirectional"))
    )
    (net (code "70") (name "Net-(U$7-D)") (class "Default")
      (node (ref "R30") (pin "2") (pinfunction "2_2") (pintype "passive"))
      (node (ref "U$7") (pin "P$3") (pinfunction "D_P$3") (pintype "bidirectional"))
    )
    (net (code "71") (name "Net-(U$7-G)") (class "Default")
      (node (ref "R20") (pin "1") (pinfunction "1_1") (pintype "passive"))
      (node (ref "U$7") (pin "P$1") (pinfunction "G_P$1") (pintype "bidirectional"))
    )
    (net (code "72") (name "Net-(U$7-S)") (class "Default")
      (node (ref "R3") (pin "1") (pinfunction "1_1") (pintype "passive"))
      (node (ref "R4") (pin "1") (pinfunction "1_1") (pintype "passive"))
      (node (ref "U$18") (pin "3") (pinfunction "3_3") (pintype "bidirectional"))
      (node (ref "U$7") (pin "P$2") (pinfunction "S_P$2") (pintype "bidirectional"))
    )
    (net (code "73") (name "Net-(U$8-D)") (class "Default")
      (node (ref "R31") (pin "2") (pinfunction "2_2") (pintype "passive"))
      (node (ref "U$8") (pin "P$3") (pinfunction "D_P$3") (pintype "bidirectional"))
    )
    (net (code "74") (name "Net-(U$8-G)") (class "Default")
      (node (ref "R6") (pin "1") (pinfunction "1_1") (pintype "passive"))
      (node (ref "U$8") (pin "P$1") (pinfunction "G_P$1") (pintype "bidirectional"))
    )
    (net (code "75") (name "Net-(U$8-S)") (class "Default")
      (node (ref "R30") (pin "1") (pinfunction "1_1") (pintype "passive"))
      (node (ref "R5") (pin "1") (pinfunction "1_1") (pintype "passive"))
      (node (ref "U$18") (pin "4") (pinfunction "4_4") (pintype "bidirectional"))
      (node (ref "U$8") (pin "P$2") (pinfunction "S_P$2") (pintype "bidirectional"))
    )
    (net (code "76") (name "Net-(U$9-D)") (class "Default")
      (node (ref "R32") (pin "2") (pinfunction "2_2") (pintype "passive"))
      (node (ref "U$9") (pin "P$3") (pinfunction "D_P$3") (pintype "bidirectional"))
    )
    (net (code "77") (name "Net-(U$9-G)") (class "Default")
      (node (ref "R8") (pin "1") (pinfunction "1_1") (pintype "passive"))
      (node (ref "U$9") (pin "P$1") (pinfunction "G_P$1") (pintype "bidirectional"))
    )
    (net (code "78") (name "Net-(U$9-S)") (class "Default")
      (node (ref "R31") (pin "1") (pinfunction "1_1") (pintype "passive"))
      (node (ref "R7") (pin "1") (pinfunction "1_1") (pintype "passive"))
      (node (ref "U$18") (pin "5") (pinfunction "5_5") (pintype "bidirectional"))
      (node (ref "U$9") (pin "P$2") (pinfunction "S_P$2") (pintype "bidirectional"))
    )
    (net (code "79") (name "Net-(U$10-D)") (class "Default")
      (node (ref "R33") (pin "2") (pinfunction "2_2") (pintype "passive"))
      (node (ref "U$10") (pin "P$3") (pinfunction "D_P$3") (pintype "bidirectional"))
    )
    (net (code "80") (name "Net-(U$10-G)") (class "Default")
      (node (ref "R10") (pin "1") (pinfunction "1_1") (pintype "passive"))
      (node (ref "U$10") (pin "P$1") (pinfunction "G_P$1") (pintype "bidirectional"))
    )
    (net (code "81") (name "Net-(U$10-S)") (class "Default")
      (node (ref "R32") (pin "1") (pinfunction "1_1") (pintype "passive"))
      (node (ref "R9") (pin "1") (pinfunction "1_1") (pintype "passive"))
      (node (ref "U$10") (pin "P$2") (pinfunction "S_P$2") (pintype "bidirectional"))
      (node (ref "U$18") (pin "6") (pinfunction "6_6") (pintype "bidirectional"))
    )
    (net (code "82") (name "Net-(U$11-D)") (class "Default")
      (node (ref "R34") (pin "2") (pinfunction "2_2") (pintype "passive"))
      (node (ref "U$11") (pin "P$3") (pinfunction "D_P$3") (pintype "bidirectional"))
    )
    (net (code "83") (name "Net-(U$11-G)") (class "Default")
      (node (ref "R12") (pin "1") (pinfunction "1_1") (pintype "passive"))
      (node (ref "U$11") (pin "P$1") (pinfunction "G_P$1") (pintype "bidirectional"))
    )
    (net (code "84") (name "Net-(U$11-S)") (class "Default")
      (node (ref "R11") (pin "1") (pinfunction "1_1") (pintype "passive"))
      (node (ref "R33") (pin "1") (pinfunction "1_1") (pintype "passive"))
      (node (ref "U$11") (pin "P$2") (pinfunction "S_P$2") (pintype "bidirectional"))
      (node (ref "U$18") (pin "7") (pinfunction "7_7") (pintype "bidirectional"))
    )
    (net (code "85") (name "Net-(U$12-D)") (class "Default")
      (node (ref "R35") (pin "2") (pinfunction "2_2") (pintype "passive"))
      (node (ref "U$12") (pin "P$3") (pinfunction "D_P$3") (pintype "bidirectional"))
    )
    (net (code "86") (name "Net-(U$12-G)") (class "Default")
      (node (ref "R19") (pin "1") (pinfunction "1_1") (pintype "passive"))
      (node (ref "U$12") (pin "P$1") (pinfunction "G_P$1") (pintype "bidirectional"))
    )
    (net (code "87") (name "Net-(U$12-S)") (class "Default")
      (node (ref "R18") (pin "1") (pinfunction "1_1") (pintype "passive"))
      (node (ref "R34") (pin "1") (pinfunction "1_1") (pintype "passive"))
      (node (ref "U$12") (pin "P$2") (pinfunction "S_P$2") (pintype "bidirectional"))
      (node (ref "U$18") (pin "8") (pinfunction "8_8") (pintype "bidirectional"))
    )
    (net (code "88") (name "Net-(U$13-D)") (class "Default")
      (node (ref "R36") (pin "2") (pinfunction "2_2") (pintype "passive"))
      (node (ref "U$13") (pin "P$3") (pinfunction "D_P$3") (pintype "bidirectional"))
    )
    (net (code "89") (name "Net-(U$13-G)") (class "Default")
      (node (ref "R22") (pin "1") (pinfunction "1_1") (pintype "passive"))
      (node (ref "U$13") (pin "P$1") (pinfunction "G_P$1") (pintype "bidirectional"))
    )
    (net (code "90") (name "Net-(U$13-S)") (class "Default")
      (node (ref "R21") (pin "1") (pinfunction "1_1") (pintype "passive"))
      (node (ref "R35") (pin "1") (pinfunction "1_1") (pintype "passive"))
      (node (ref "U$13") (pin "P$2") (pinfunction "S_P$2") (pintype "bidirectional"))
      (node (ref "U$18") (pin "9") (pinfunction "9_9") (pintype "bidirectional"))
    )
    (net (code "91") (name "Net-(U$15-D)") (class "Default")
      (node (ref "R37") (pin "2") (pinfunction "2_2") (pintype "passive"))
      (node (ref "U$15") (pin "P$3") (pinfunction "D_P$3") (pintype "bidirectional"))
    )
    (net (code "92") (name "Net-(U$15-G)") (class "Default")
      (node (ref "R24") (pin "1") (pinfunction "1_1") (pintype "passive"))
      (node (ref "U$15") (pin "P$1") (pinfunction "G_P$1") (pintype "bidirectional"))
    )
    (net (code "93") (name "Net-(U$15-S)") (class "Default")
      (node (ref "R23") (pin "1") (pinfunction "1_1") (pintype "passive"))
      (node (ref "R36") (pin "1") (pinfunction "1_1") (pintype "passive"))
      (node (ref "U$15") (pin "P$2") (pinfunction "S_P$2") (pintype "bidirectional"))
      (node (ref "U$18") (pin "10") (pinfunction "10_10") (pintype "bidirectional"))
    )
    (net (code "94") (name "Net-(U$16-D)") (class "Default")
      (node (ref "R38") (pin "2") (pinfunction "2_2") (pintype "passive"))
      (node (ref "U$16") (pin "P$3") (pinfunction "D_P$3") (pintype "bidirectional"))
    )
    (net (code "95") (name "Net-(U$16-G)") (class "Default")
      (node (ref "R26") (pin "1") (pinfunction "1_1") (pintype "passive"))
      (node (ref "U$16") (pin "P$1") (pinfunction "G_P$1") (pintype "bidirectional"))
    )
    (net (code "96") (name "Net-(U$16-S)") (class "Default")
      (node (ref "R25") (pin "1") (pinfunction "1_1") (pintype "passive"))
      (node (ref "R37") (pin "1") (pinfunction "1_1") (pintype "passive"))
      (node (ref "U$16") (pin "P$2") (pinfunction "S_P$2") (pintype "bidirectional"))
      (node (ref "U$18") (pin "11") (pinfunction "11_11") (pintype "bidirectional"))
    )
    (net (code "97") (name "Net-(U$17-D)") (class "Default")
      (node (ref "R39") (pin "2") (pinfunction "2_2") (pintype "passive"))
      (node (ref "U$17") (pin "P$3") (pinfunction "D_P$3") (pintype "bidirectional"))
    )
    (net (code "98") (name "Net-(U$17-G)") (class "Default")
      (node (ref "R28") (pin "1") (pinfunction "1_1") (pintype "passive"))
      (node (ref "U$17") (pin "P$1") (pinfunction "G_P$1") (pintype "bidirectional"))
    )
    (net (code "99") (name "Net-(U$17-S)") (class "Default")
      (node (ref "R27") (pin "1") (pinfunction "1_1") (pintype "passive"))
      (node (ref "R38") (pin "1") (pinfunction "1_1") (pintype "passive"))
      (node (ref "U$17") (pin "P$2") (pinfunction "S_P$2") (pintype "bidirectional"))
      (node (ref "U$18") (pin "12") (pinfunction "12_12") (pintype "bidirectional"))
    )
    (net (code "100") (name "Net-(U$19-Pad5)") (class "Default")
      (node (ref "U$19") (pin "5") (pinfunction "5_5") (pintype "bidirectional"))
      (node (ref "U$2") (pin "5") (pinfunction "5_5") (pintype "bidirectional"))
    )
    (net (code "101") (name "unconnected-(SN65-RX1-PadP$5)") (class "Default")
      (node (ref "SN65") (pin "P$5") (pinfunction "RX1_P$5") (pintype "bidirectional"))
    )
    (net (code "102") (name "unconnected-(U$1-GPIO1-Pad35)") (class "Default")
      (node (ref "U$1") (pin "35") (pinfunction "GPIO1_35") (pintype "bidirectional"))
    )
    (net (code "103") (name "unconnected-(U$1-GPIO2-Pad36)") (class "Default")
      (node (ref "U$1") (pin "36") (pinfunction "GPIO2_36") (pintype "bidirectional"))
    )
    (net (code "104") (name "unconnected-(U$1-WDTB-Pad34)") (class "Default")
      (node (ref "U$1") (pin "34") (pinfunction "WDTB_34") (pintype "bidirectional"))
    )
    (net (code "105") (name "unconnected-(U$3-AREF(ISRC)-Pad21)") (class "Default")
      (node (ref "U$3") (pin "21") (pinfunction "AREF(ISRC)_21") (pintype "bidirectional"))
    )
    (net (code "106") (name "unconnected-(U$3-PB1(MOSI{slash}PSCOUT2B)-Pad9)") (class "Default")
      (node (ref "U$3") (pin "9") (pinfunction "PB1(MOSI/PSCOUT2B)_9") (pintype "bidirectional"))
    )
    (net (code "107") (name "unconnected-(U$3-PB5(ADC6{slash}INT2{slash}ACMPN1{slash}AMP2-)-Pad26)") (class "Default")
      (node (ref "U$3") (pin "26") (pinfunction "PB5(ADC6/INT2/ACMPN1/AMP2-)_26") (pintype "bidirectional"))
    )
    (net (code "108") (name "unconnected-(U$3-PB6(ADC7{slash}PSCOUT1B)-Pad27)") (class "Default")
      (node (ref "U$3") (pin "27") (pinfunction "PB6(ADC7/PSCOUT1B)_27") (pintype "bidirectional"))
    )
    (net (code "109") (name "unconnected-(U$3-PB7(ADC4{slash}PSCOUT0B{slash}SCK)-Pad28)") (class "Default")
      (node (ref "U$3") (pin "28") (pinfunction "PB7(ADC4/PSCOUT0B/SCK)_28") (pintype "bidirectional"))
    )
    (net (code "110") (name "unconnected-(U$3-PC0(INT3{slash}PSCOUT1A)-Pad30)") (class "Default")
      (node (ref "U$3") (pin "30") (pinfunction "PC0(INT3/PSCOUT1A)_30") (pintype "bidirectional"))
    )
    (net (code "111") (name "unconnected-(U$3-PD0(PSCOUT0A)-Pad29)") (class "Default")
      (node (ref "U$3") (pin "29") (pinfunction "PD0(PSCOUT0A)_29") (pintype "bidirectional"))
    )
    (net (code "112") (name "unconnected-(U$3-PD5(ADC2{slash}ACMP2)-Pad13)") (class "Default")
      (node (ref "U$3") (pin "13") (pinfunction "PD5(ADC2/ACMP2)_13") (pintype "bidirectional"))
    )
    (net (code "113") (name "unconnected-(U$3-PD6(ADC3{slash}ACMPN2{slash}INT0)-Pad14)") (class "Default")
      (node (ref "U$3") (pin "14") (pinfunction "PD6(ADC3/ACMPN2/INT0)_14") (pintype "bidirectional"))
    )
    (net (code "114") (name "unconnected-(U$14-CTRL1-Pad7)") (class "Default")
      (node (ref "U$14") (pin "7") (pinfunction "CTRL1_7") (pintype "bidirectional"))
    )
    (net (code "115") (name "unconnected-(U$14-CTRL2-Pad10)") (class "Default")
      (node (ref "U$14") (pin "10") (pinfunction "CTRL2_10") (pintype "bidirectional"))
    )
  )
)
